# BlueSource_01.net
KiCad netlist of a schematic drawn in Altium Designer
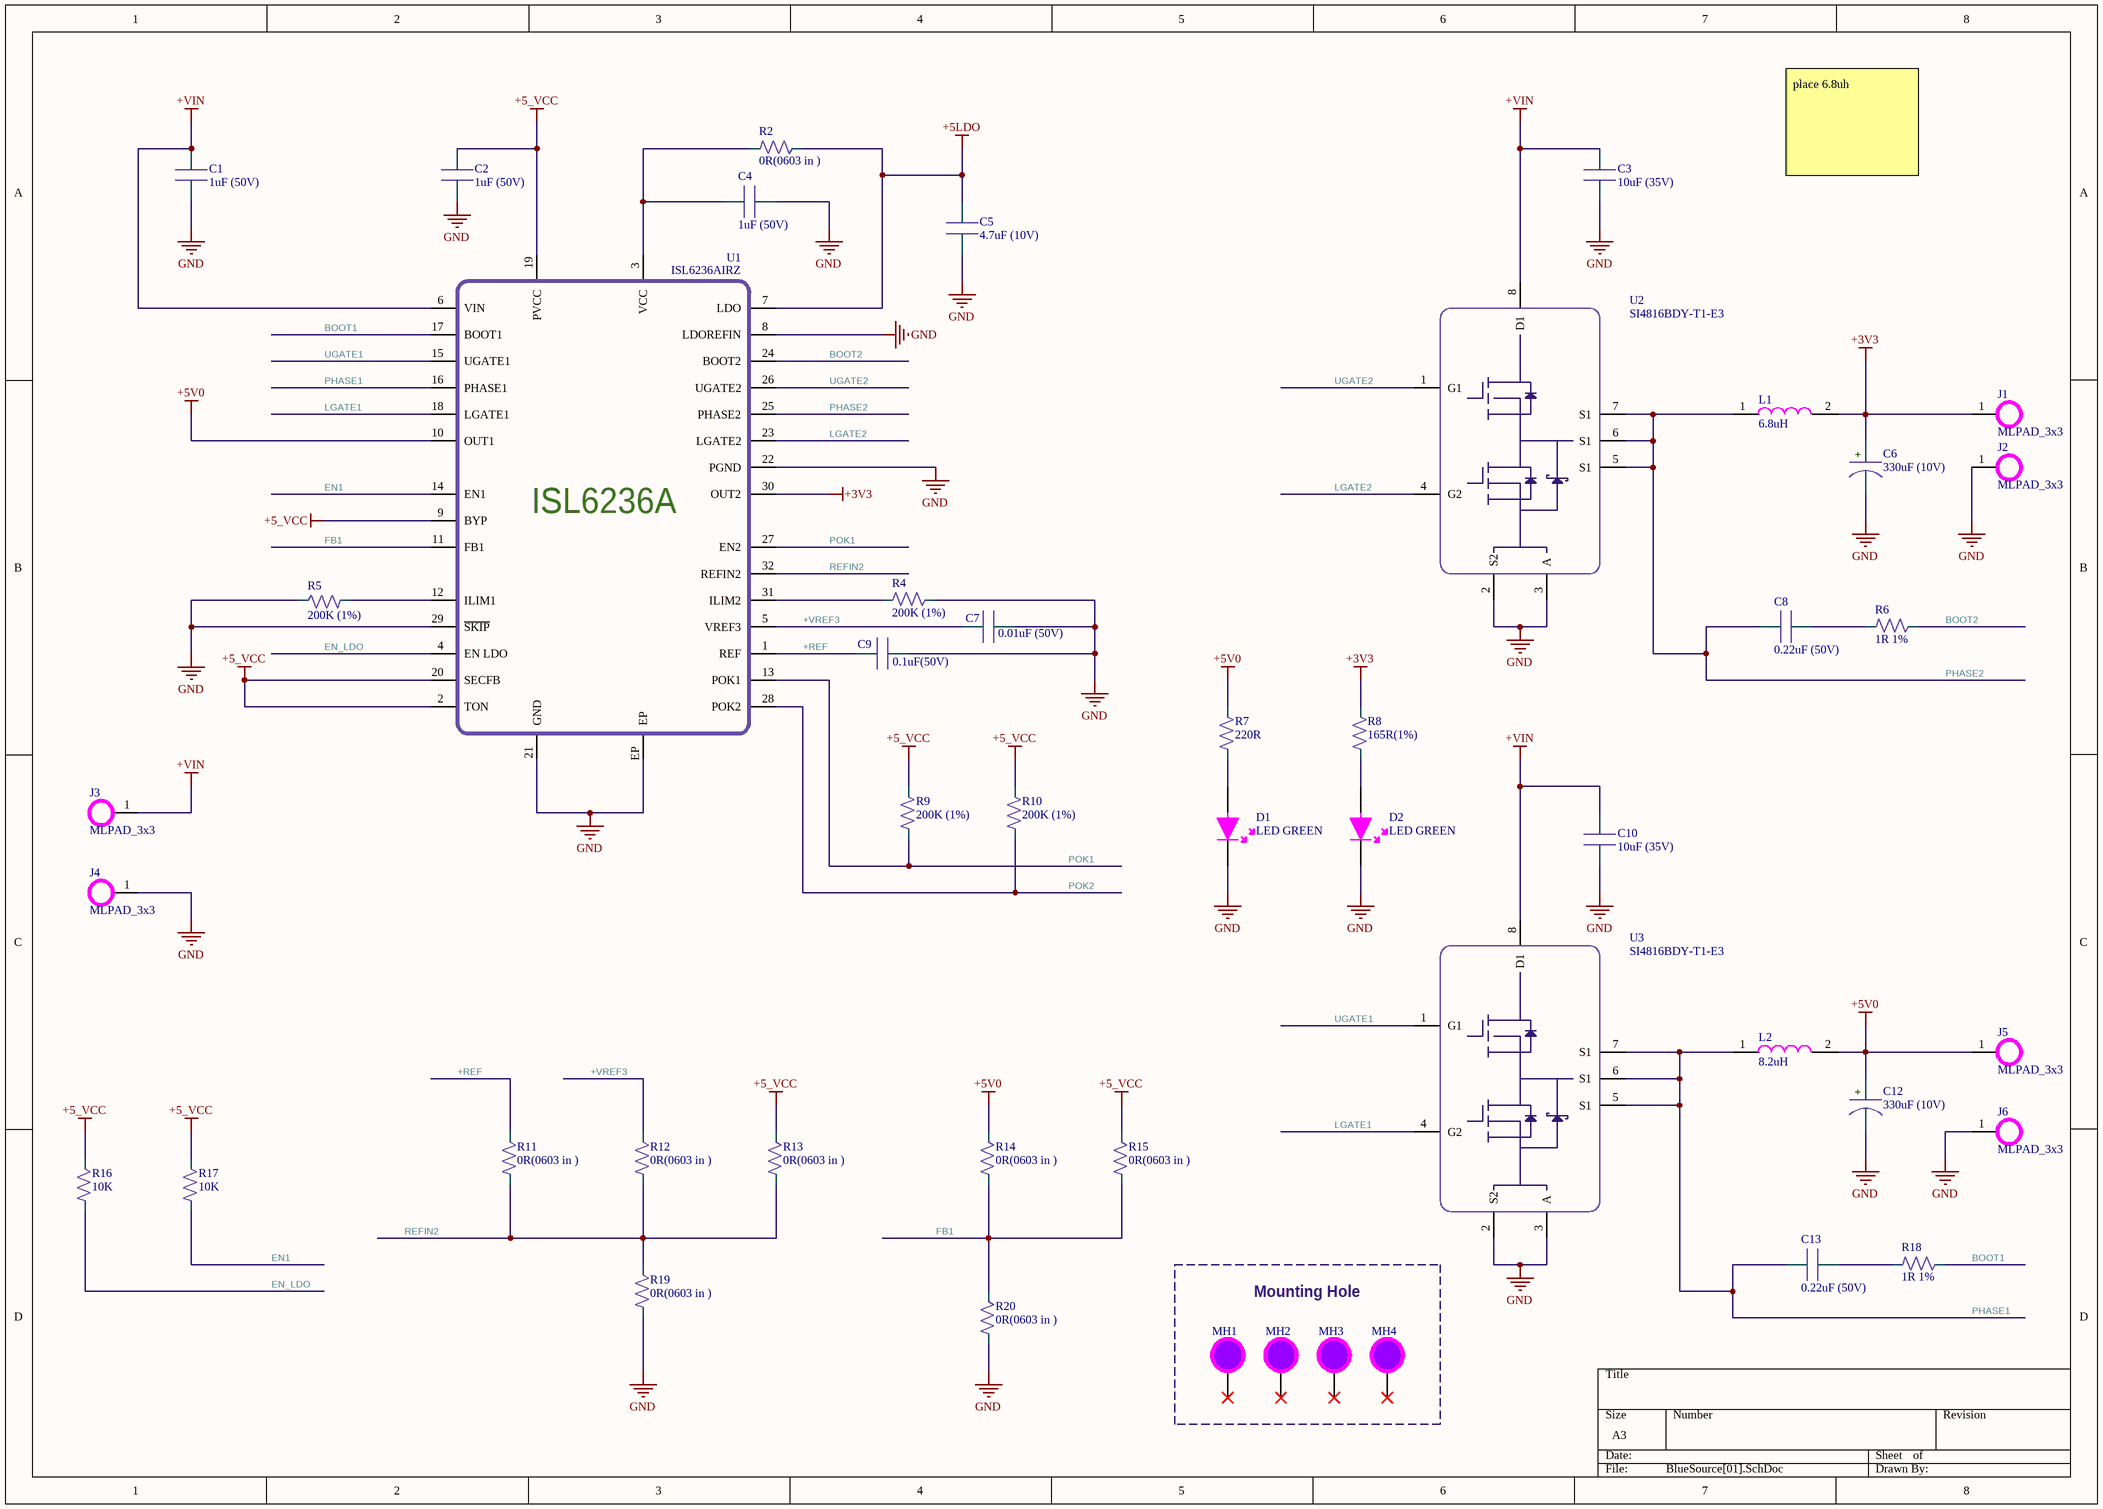
[diagram p0: BlueSource[01].SchDoc]

(export (version "E")
  (design (tool "Eeschema 10.0.6"))
  (components
    (comp (ref "C1")
      (value "1uF (50V)")
      (footprint "Capacitor_0805")
      (description "1µF ±5% 50V Ceramic Capacitor X7R 0805 (2012 Metric)")
      (fields
        (field (name "MANUFACTURERPARTNUMBER") "CC0805JKX7R9BB105")
        (field (name "MANUFACTURER") "Yageo")
      )
      (libsource (lib "Capacitors") (part "CC0805JKX7R9BB105"))
    )
    (comp (ref "C2")
      (value "1uF (50V)")
      (footprint "Capacitor_0805")
      (description "1µF ±5% 50V Ceramic Capacitor X7R 0805 (2012 Metric)")
      (fields
        (field (name "MANUFACTURERPARTNUMBER") "CC0805JKX7R9BB105")
        (field (name "MANUFACTURER") "Yageo")
      )
      (libsource (lib "Capacitors") (part "CC0805JKX7R9BB105"))
    )
    (comp (ref "C3")
      (value "10uF (35V)")
      (footprint "Capacitor_0805")
      (description "10µF ±10% 35V Ceramic Capacitor X5R 0805 (2012 Metric)")
      (fields
        (field (name "MANUFACTURERPARTNUMBER") "C2012X5R1V106K125AC")
        (field (name "MANUFACTURER") "TDK Corporation")
      )
      (libsource (lib "Capacitors") (part "C2012X5R1V106K125AC"))
    )
    (comp (ref "C4")
      (value "1uF (50V)")
      (footprint "Capacitor_0805")
      (description "1µF ±5% 50V Ceramic Capacitor X7R 0805 (2012 Metric)")
      (fields
        (field (name "MANUFACTURERPARTNUMBER") "CC0805JKX7R9BB105")
        (field (name "MANUFACTURER") "Yageo")
      )
      (libsource (lib "Capacitors") (part "CC0805JKX7R9BB105"))
    )
    (comp (ref "C5")
      (value "4.7uF (10V)")
      (footprint "Capacitor_0805")
      (description "4.7µF ±5% 10V Ceramic Capacitor X7R 0805 (2012 Metric)")
      (fields
        (field (name "MANUFACTURERPARTNUMBER") "C0805C475J8RACAUTO")
        (field (name "MANUFACTURER") "KEMET")
      )
      (libsource (lib "Capacitors") (part "C0805C475J8RACAUTO"))
    )
    (comp (ref "C6")
      (value "330uF (10V)")
      (footprint "C7343")
      (description "330µF Molded Tantalum Polymer Capacitor 10V 2917 (7343 Metric) 4mOhm @ 100kHz")
      (fields
        (field (name "MANUFACTURERPARTNUMBER") "T530X337M010ATE004")
        (field (name "MANUFACTURER") "KEMET")
      )
      (libsource (lib "Capacitors") (part "T530X337M010ATE004"))
    )
    (comp (ref "C7")
      (value "0.01uF (50V)")
      (footprint "Capacitor_0805")
      (description "10000pF ±5% 50V Ceramic Capacitor X8R 0805 (2012 Metric)")
      (fields
        (field (name "MANUFACTURERPARTNUMBER") "C0805C103J5HACAUTO")
        (field (name "MANUFACTURER") "KEMET")
      )
      (libsource (lib "Capacitors") (part "C0805C103J5HACAUTO"))
    )
    (comp (ref "C8")
      (value "0.22uF (50V)")
      (footprint "Capacitor_0805")
      (description "0.22µF ±5% 50V Ceramic Capacitor X7R 0805 (2012 Metric)")
      (fields
        (field (name "MANUFACTURERPARTNUMBER") "C0805C224J5RACAUTO")
        (field (name "MANUFACTURER") "399-C0805C224J5RACAUTOCT-ND")
      )
      (libsource (lib "Capacitors") (part "C0805C224J5RACAUTO"))
    )
    (comp (ref "C9")
      (value "0.1uF(50V)")
      (footprint "Capacitor_0805")
      (description "0.1µF ±5% 50V Ceramic Capacitor X7R 0805 (2012 Metric)")
      (fields
        (field (name "MANUFACTURERPARTNUMBER") "C0805C104J5RACTU")
        (field (name "MANUFACTURER") "KEMET")
      )
      (libsource (lib "Capacitors") (part "C0805C104J5RACTU"))
    )
    (comp (ref "C10")
      (value "10uF (35V)")
      (footprint "Capacitor_0805")
      (description "10µF ±10% 35V Ceramic Capacitor X5R 0805 (2012 Metric)")
      (fields
        (field (name "MANUFACTURERPARTNUMBER") "C2012X5R1V106K125AC")
        (field (name "MANUFACTURER") "TDK Corporation")
      )
      (libsource (lib "Capacitors") (part "C2012X5R1V106K125AC"))
    )
    (comp (ref "C12")
      (value "330uF (10V)")
      (footprint "C7343")
      (description "330µF Molded Tantalum Polymer Capacitor 10V 2917 (7343 Metric) 4mOhm @ 100kHz")
      (fields
        (field (name "MANUFACTURERPARTNUMBER") "T530X337M010ATE004")
        (field (name "MANUFACTURER") "KEMET")
      )
      (libsource (lib "Capacitors") (part "T530X337M010ATE004"))
    )
    (comp (ref "C13")
      (value "0.22uF (50V)")
      (footprint "Capacitor_0805")
      (description "0.22µF ±5% 50V Ceramic Capacitor X7R 0805 (2012 Metric)")
      (fields
        (field (name "MANUFACTURERPARTNUMBER") "C0805C224J5RACAUTO")
        (field (name "MANUFACTURER") "399-C0805C224J5RACAUTOCT-ND")
      )
      (libsource (lib "Capacitors") (part "C0805C224J5RACAUTO"))
    )
    (comp (ref "D1")
      (value "LED GREEN")
      (footprint "0603_LED")
      (description "Green 570nm LED Indication - Discrete 2.1V 0603 (1608 Metric)")
      (fields (field (name "MANUFACTURER PART NUMBER") "XZVG53W-8"))
      (libsource (lib "Diodes") (part "XZVG53W-8"))
    )
    (comp (ref "D2")
      (value "LED GREEN")
      (footprint "0603_LED")
      (description "Green 570nm LED Indication - Discrete 2.1V 0603 (1608 Metric)")
      (fields (field (name "MANUFACTURER PART NUMBER") "XZVG53W-8"))
      (libsource (lib "Diodes") (part "XZVG53W-8"))
    )
    (comp (ref "J1")
      (value "MLPAD_3x3")
      (footprint "MLPAD_3X3")
      (libsource (lib "connectors") (part "MLPAD_3X3"))
    )
    (comp (ref "J2")
      (value "MLPAD_3x3")
      (footprint "MLPAD_3X3")
      (libsource (lib "connectors") (part "MLPAD_3X3"))
    )
    (comp (ref "J3")
      (value "MLPAD_3x3")
      (footprint "MLPAD_3X3")
      (libsource (lib "connectors") (part "MLPAD_3X3"))
    )
    (comp (ref "J4")
      (value "MLPAD_3x3")
      (footprint "MLPAD_3X3")
      (libsource (lib "connectors") (part "MLPAD_3X3"))
    )
    (comp (ref "J5")
      (value "MLPAD_3x3")
      (footprint "MLPAD_3X3")
      (libsource (lib "connectors") (part "MLPAD_3X3"))
    )
    (comp (ref "J6")
      (value "MLPAD_3x3")
      (footprint "MLPAD_3X3")
      (libsource (lib "connectors") (part "MLPAD_3X3"))
    )
    (comp (ref "L1")
      (value "6.8uH")
      (footprint "DR125_Inductor")
      (description "6.8µH Shielded Wirewound Inductor 6.64A 12.3mOhm Nonstandard")
      (fields
        (field (name "MANUFACTURERPARTNUMBER") "DR125-6R8-R")
        (field (name "MANUFACTURER") "Eaton - Electronics Division")
      )
      (libsource (lib "inductors and coils") (part "DR125-6R8-R"))
    )
    (comp (ref "L2")
      (value "8.2uH")
      (footprint "DR125_Inductor")
      (description "8.2µH Shielded Wirewound Inductor 5.54A 17.6mOhm Nonstandard")
      (fields
        (field (name "MANUFACTURERPARTNUMBER") "DR125-8R2-R")
        (field (name "MANUFACTURER") "Eaton - Electronics Division")
      )
      (libsource (lib "inductors and coils") (part "DR125-8R2-R"))
    )
    (comp (ref "MH1")
      (value "Mounting Hole")
      (footprint "Mounting_Hole_3.3mm")
      (description "3.3mm Mounting Hole")
      (libsource (lib "connectors") (part "3MM_MOUNTING_HOLE"))
    )
    (comp (ref "MH2")
      (value "Mounting Hole")
      (footprint "Mounting_Hole_3.3mm")
      (description "3.3mm Mounting Hole")
      (libsource (lib "connectors") (part "3MM_MOUNTING_HOLE"))
    )
    (comp (ref "MH3")
      (value "Mounting Hole")
      (footprint "Mounting_Hole_3.3mm")
      (description "3.3mm Mounting Hole")
      (libsource (lib "connectors") (part "3MM_MOUNTING_HOLE"))
    )
    (comp (ref "MH4")
      (value "Mounting Hole")
      (footprint "Mounting_Hole_3.3mm")
      (description "3.3mm Mounting Hole")
      (libsource (lib "connectors") (part "3MM_MOUNTING_HOLE"))
    )
    (comp (ref "R2")
      (value "0R(0603 in )")
      (footprint "RESISTOR0603")
      (description "0 Ohms Jumper 0.1W, 1/10W Chip Resistor 0603 (1608 Metric) Automotive AEC-Q200 Thick Film")
      (fields (field (name "MANUFACTURER PART NUMBER") "RMCF0603ZT0R00"))
      (libsource (lib "Resistors") (part "RMCF0603ZT0R00"))
    )
    (comp (ref "R4")
      (value "200K (1%)")
      (footprint "RESISTOR0805")
      (description "200 kOhms ±1% 0.125W, 1/8W Chip Resistor 0805 (2012 Metric) Automotive AEC-Q200 Thick Film")
      (fields
        (field (name "MANUFACTURERPARTNUMBER") "ERJ-6ENF2003V")
        (field (name "MANUFACTURER") "Panasonic Electronic Components")
      )
      (libsource (lib "Resistors") (part "ERJ-6ENF2003V"))
    )
    (comp (ref "R5")
      (value "200K (1%)")
      (footprint "RESISTOR0805")
      (description "200 kOhms ±1% 0.125W, 1/8W Chip Resistor 0805 (2012 Metric) Automotive AEC-Q200 Thick Film")
      (fields
        (field (name "MANUFACTURERPARTNUMBER") "ERJ-6ENF2003V")
        (field (name "MANUFACTURER") "Panasonic Electronic Components")
      )
      (libsource (lib "Resistors") (part "ERJ-6ENF2003V"))
    )
    (comp (ref "R6")
      (value "1R 1%")
      (footprint "RESISTOR0805")
      (fields
        (field (name "MANUFACTURERPARTNUMBER") "ERJ-6RQF1R0V")
        (field (name "MANUFACTURER") "Panasonic Electronic Components")
      )
      (libsource (lib "Resistors") (part "ERJ-6RQF1R0V"))
    )
    (comp (ref "R7")
      (value "220R")
      (footprint "RESISTOR0603")
      (description "220 Ohms ±5% 0.1W, 1/10W Chip Resistor 0603 (1608 Metric) Automotive AEC-Q200 Thick Film")
      (fields
        (field (name "MANUFACTURERPARTNUMBER") "RMCF0603JT220R")
        (field (name "MANUFACTURER") "Stackpole Electronics Inc")
      )
      (libsource (lib "Resistors") (part "RMCF0603JT220R"))
    )
    (comp (ref "R8")
      (value "165R(1%)")
      (footprint "RESISTOR0603")
      (description "165 Ohms ±1% 0.1W, 1/10W Chip Resistor 0603 (1608 Metric) Automotive AEC-Q200 Thick Film")
      (fields
        (field (name "MANUFACTURERPARTNUMBER") "RMCF0603FT165R")
        (field (name "MANUFACTURER") "Stackpole Electronics Inc")
      )
      (libsource (lib "Resistors") (part "RMCF0603FT165R"))
    )
    (comp (ref "R9")
      (value "200K (1%)")
      (footprint "RESISTOR0805")
      (description "200 kOhms ±1% 0.125W, 1/8W Chip Resistor 0805 (2012 Metric) Automotive AEC-Q200 Thick Film")
      (fields
        (field (name "MANUFACTURERPARTNUMBER") "ERJ-6ENF2003V")
        (field (name "MANUFACTURER") "Panasonic Electronic Components")
      )
      (libsource (lib "Resistors") (part "ERJ-6ENF2003V"))
    )
    (comp (ref "R10")
      (value "200K (1%)")
      (footprint "RESISTOR0805")
      (description "200 kOhms ±1% 0.125W, 1/8W Chip Resistor 0805 (2012 Metric) Automotive AEC-Q200 Thick Film")
      (fields
        (field (name "MANUFACTURERPARTNUMBER") "ERJ-6ENF2003V")
        (field (name "MANUFACTURER") "Panasonic Electronic Components")
      )
      (libsource (lib "Resistors") (part "ERJ-6ENF2003V"))
    )
    (comp (ref "R11")
      (value "0R(0603 in )")
      (footprint "RESISTOR0603")
      (description "0 Ohms Jumper 0.1W, 1/10W Chip Resistor 0603 (1608 Metric) Automotive AEC-Q200 Thick Film")
      (fields (field (name "MANUFACTURER PART NUMBER") "RMCF0603ZT0R00"))
      (libsource (lib "Resistors") (part "RMCF0603ZT0R00"))
    )
    (comp (ref "R12")
      (value "0R(0603 in )")
      (footprint "RESISTOR0603")
      (description "0 Ohms Jumper 0.1W, 1/10W Chip Resistor 0603 (1608 Metric) Automotive AEC-Q200 Thick Film")
      (fields (field (name "MANUFACTURER PART NUMBER") "RMCF0603ZT0R00"))
      (libsource (lib "Resistors") (part "RMCF0603ZT0R00"))
    )
    (comp (ref "R13")
      (value "0R(0603 in )")
      (footprint "RESISTOR0603")
      (description "0 Ohms Jumper 0.1W, 1/10W Chip Resistor 0603 (1608 Metric) Automotive AEC-Q200 Thick Film")
      (fields (field (name "MANUFACTURER PART NUMBER") "RMCF0603ZT0R00"))
      (libsource (lib "Resistors") (part "RMCF0603ZT0R00"))
    )
    (comp (ref "R14")
      (value "0R(0603 in )")
      (footprint "RESISTOR0603")
      (description "0 Ohms Jumper 0.1W, 1/10W Chip Resistor 0603 (1608 Metric) Automotive AEC-Q200 Thick Film")
      (fields (field (name "MANUFACTURER PART NUMBER") "RMCF0603ZT0R00"))
      (libsource (lib "Resistors") (part "RMCF0603ZT0R00"))
    )
    (comp (ref "R15")
      (value "0R(0603 in )")
      (footprint "RESISTOR0603")
      (description "0 Ohms Jumper 0.1W, 1/10W Chip Resistor 0603 (1608 Metric) Automotive AEC-Q200 Thick Film")
      (fields (field (name "MANUFACTURER PART NUMBER") "RMCF0603ZT0R00"))
      (libsource (lib "Resistors") (part "RMCF0603ZT0R00"))
    )
    (comp (ref "R16")
      (value "10K")
      (footprint "RESISTOR0805")
      (description "10 kOhms ±5% 0.125W, 1/8W Chip Resistor 0805 (2012 Metric) Automotive AEC-Q200 Thick Film")
      (fields
        (field (name "MANUFACTURERPARTNUMBER") "ERJ-6GEYJ103V")
        (field (name "MANUFACTURER") "Panasonic Electronic Components")
      )
      (libsource (lib "Resistors") (part "ERJ-6GEYJ103V"))
    )
    (comp (ref "R17")
      (value "10K")
      (footprint "RESISTOR0805")
      (description "10 kOhms ±5% 0.125W, 1/8W Chip Resistor 0805 (2012 Metric) Automotive AEC-Q200 Thick Film")
      (fields
        (field (name "MANUFACTURERPARTNUMBER") "ERJ-6GEYJ103V")
        (field (name "MANUFACTURER") "Panasonic Electronic Components")
      )
      (libsource (lib "Resistors") (part "ERJ-6GEYJ103V"))
    )
    (comp (ref "R18")
      (value "1R 1%")
      (footprint "RESISTOR0805")
      (fields
        (field (name "MANUFACTURERPARTNUMBER") "ERJ-6RQF1R0V")
        (field (name "MANUFACTURER") "Panasonic Electronic Components")
      )
      (libsource (lib "Resistors") (part "ERJ-6RQF1R0V"))
    )
    (comp (ref "R19")
      (value "0R(0603 in )")
      (footprint "RESISTOR0603")
      (description "0 Ohms Jumper 0.1W, 1/10W Chip Resistor 0603 (1608 Metric) Automotive AEC-Q200 Thick Film")
      (fields (field (name "MANUFACTURER PART NUMBER") "RMCF0603ZT0R00"))
      (libsource (lib "Resistors") (part "RMCF0603ZT0R00"))
    )
    (comp (ref "R20")
      (value "0R(0603 in )")
      (footprint "RESISTOR0603")
      (description "0 Ohms Jumper 0.1W, 1/10W Chip Resistor 0603 (1608 Metric) Automotive AEC-Q200 Thick Film")
      (fields (field (name "MANUFACTURER PART NUMBER") "RMCF0603ZT0R00"))
      (libsource (lib "Resistors") (part "RMCF0603ZT0R00"))
    )
    (comp (ref "U1")
      (value "ISL6236AIRZ")
      (footprint "32QFN")
      (description "- Controller, Notebook Power System Voltage Regulator IC 4 Output 32-QFN (5x5)")
      (fields (field (name "MANUFACTURER") "Renesas Electronics America Inc"))
      (libsource (lib "integrated_circuits") (part "ISL6236AIRZ"))
    )
    (comp (ref "U2")
      (value "SI4816BDY-T1-E3")
      (footprint "SOIC-8")
      (description "Mosfet Array 2 N-Channel (Half Bridge) 30V 5.8A, 8.2A 1W, 1.25W Surface Mount 8-SO")
      (fields (field (name "MANUFACTURER") "Vishay Siliconix"))
      (libsource (lib "integrated_circuits") (part "SI4816BDY-T1-E3"))
    )
    (comp (ref "U3")
      (value "SI4816BDY-T1-E3")
      (footprint "SOIC-8")
      (description "Mosfet Array 2 N-Channel (Half Bridge) 30V 5.8A, 8.2A 1W, 1.25W Surface Mount 8-SO")
      (fields (field (name "MANUFACTURER") "Vishay Siliconix"))
      (libsource (lib "integrated_circuits") (part "SI4816BDY-T1-E3"))
    )
  )
  (nets
    (net (code "1") (name "+3V3") (class "Default")
      (node (ref "C6") (pin "2") (pinfunction "2_2") (pintype "passive"))
      (node (ref "J1") (pin "1") (pinfunction "1_1") (pintype "passive"))
      (node (ref "L1") (pin "2") (pinfunction "2_2") (pintype "passive"))
      (node (ref "R8") (pin "2") (pinfunction "2_2") (pintype "passive"))
      (node (ref "U1") (pin "30") (pinfunction "OUT2_30") (pintype "passive"))
    )
    (net (code "2") (name "+5LDO") (class "Default")
      (node (ref "C5") (pin "2") (pinfunction "2_2") (pintype "passive"))
      (node (ref "R2") (pin "2") (pinfunction "2_2") (pintype "passive"))
      (node (ref "U1") (pin "7") (pinfunction "LDO_7") (pintype "passive"))
    )
    (net (code "3") (name "+5V0") (class "Default")
      (node (ref "C12") (pin "2") (pinfunction "2_2") (pintype "passive"))
      (node (ref "J5") (pin "1") (pinfunction "1_1") (pintype "passive"))
      (node (ref "L2") (pin "2") (pinfunction "2_2") (pintype "passive"))
      (node (ref "R14") (pin "2") (pinfunction "2_2") (pintype "passive"))
      (node (ref "R7") (pin "2") (pinfunction "2_2") (pintype "passive"))
      (node (ref "U1") (pin "10") (pinfunction "OUT1_10") (pintype "passive"))
    )
    (net (code "4") (name "+5_VCC") (class "Default")
      (node (ref "C2") (pin "2") (pinfunction "2_2") (pintype "passive"))
      (node (ref "R10") (pin "2") (pinfunction "2_2") (pintype "passive"))
      (node (ref "R13") (pin "2") (pinfunction "2_2") (pintype "passive"))
      (node (ref "R15") (pin "2") (pinfunction "2_2") (pintype "passive"))
      (node (ref "R16") (pin "2") (pinfunction "2_2") (pintype "passive"))
      (node (ref "R17") (pin "2") (pinfunction "2_2") (pintype "passive"))
      (node (ref "R9") (pin "2") (pinfunction "2_2") (pintype "passive"))
      (node (ref "U1") (pin "19") (pinfunction "PVCC_19") (pintype "passive"))
      (node (ref "U1") (pin "2") (pinfunction "TON_2") (pintype "passive"))
      (node (ref "U1") (pin "20") (pinfunction "SECFB_20") (pintype "passive"))
      (node (ref "U1") (pin "9") (pinfunction "BYP_9") (pintype "passive"))
    )
    (net (code "5") (name "+VIN") (class "Default")
      (node (ref "C1") (pin "2") (pinfunction "2_2") (pintype "passive"))
      (node (ref "C10") (pin "2") (pinfunction "2_2") (pintype "passive"))
      (node (ref "C3") (pin "2") (pinfunction "2_2") (pintype "passive"))
      (node (ref "J3") (pin "1") (pinfunction "1_1") (pintype "passive"))
      (node (ref "U1") (pin "6") (pinfunction "VIN_6") (pintype "passive"))
      (node (ref "U2") (pin "8") (pinfunction "D1_8") (pintype "passive"))
      (node (ref "U3") (pin "8") (pinfunction "D1_8") (pintype "passive"))
    )
    (net (code "6") (name "/+REF") (class "Default")
      (node (ref "C9") (pin "1") (pinfunction "1_1") (pintype "passive"))
      (node (ref "R11") (pin "2") (pinfunction "2_2") (pintype "passive"))
      (node (ref "U1") (pin "1") (pinfunction "REF_1") (pintype "passive"))
    )
    (net (code "7") (name "/+VREF3") (class "Default")
      (node (ref "C7") (pin "1") (pinfunction "1_1") (pintype "passive"))
      (node (ref "R12") (pin "2") (pinfunction "2_2") (pintype "passive"))
      (node (ref "U1") (pin "5") (pinfunction "VREF3_5") (pintype "passive"))
    )
    (net (code "8") (name "/BOOT1") (class "Default")
      (node (ref "R18") (pin "2") (pinfunction "2_2") (pintype "passive"))
      (node (ref "U1") (pin "17") (pinfunction "BOOT1_17") (pintype "passive"))
    )
    (net (code "9") (name "/BOOT2") (class "Default")
      (node (ref "R6") (pin "2") (pinfunction "2_2") (pintype "passive"))
      (node (ref "U1") (pin "24") (pinfunction "BOOT2_24") (pintype "passive"))
    )
    (net (code "10") (name "/EN1") (class "Default")
      (node (ref "R17") (pin "1") (pinfunction "1_1") (pintype "passive"))
      (node (ref "U1") (pin "14") (pinfunction "EN1_14") (pintype "passive"))
    )
    (net (code "11") (name "/EN_LDO") (class "Default")
      (node (ref "R16") (pin "1") (pinfunction "1_1") (pintype "passive"))
      (node (ref "U1") (pin "4") (pinfunction "EN_LDO_4") (pintype "passive"))
    )
    (net (code "12") (name "/FB1") (class "Default")
      (node (ref "R14") (pin "1") (pinfunction "1_1") (pintype "passive"))
      (node (ref "R15") (pin "1") (pinfunction "1_1") (pintype "passive"))
      (node (ref "R20") (pin "2") (pinfunction "2_2") (pintype "passive"))
      (node (ref "U1") (pin "11") (pinfunction "FB1_11") (pintype "passive"))
    )
    (net (code "13") (name "/LGATE1") (class "Default")
      (node (ref "U1") (pin "18") (pinfunction "LGATE1_18") (pintype "passive"))
      (node (ref "U3") (pin "4") (pinfunction "G2_4") (pintype "passive"))
    )
    (net (code "14") (name "/LGATE2") (class "Default")
      (node (ref "U1") (pin "23") (pinfunction "LGATE2_23") (pintype "passive"))
      (node (ref "U2") (pin "4") (pinfunction "G2_4") (pintype "passive"))
    )
    (net (code "15") (name "/PHASE1") (class "Default")
      (node (ref "C13") (pin "1") (pinfunction "1_1") (pintype "passive"))
      (node (ref "L2") (pin "1") (pinfunction "1_1") (pintype "passive"))
      (node (ref "U1") (pin "16") (pinfunction "PHASE1_16") (pintype "passive"))
      (node (ref "U3") (pin "5") (pinfunction "S1_5") (pintype "passive"))
      (node (ref "U3") (pin "6") (pinfunction "S1_6") (pintype "passive"))
      (node (ref "U3") (pin "7") (pinfunction "S1_7") (pintype "passive"))
    )
    (net (code "16") (name "/PHASE2") (class "Default")
      (node (ref "C8") (pin "1") (pinfunction "1_1") (pintype "passive"))
      (node (ref "L1") (pin "1") (pinfunction "1_1") (pintype "passive"))
      (node (ref "U1") (pin "25") (pinfunction "PHASE2_25") (pintype "passive"))
      (node (ref "U2") (pin "5") (pinfunction "S1_5") (pintype "passive"))
      (node (ref "U2") (pin "6") (pinfunction "S1_6") (pintype "passive"))
      (node (ref "U2") (pin "7") (pinfunction "S1_7") (pintype "passive"))
    )
    (net (code "17") (name "/POK1") (class "Default")
      (node (ref "R9") (pin "1") (pinfunction "1_1") (pintype "passive"))
      (node (ref "U1") (pin "13") (pinfunction "POK1_13") (pintype "passive"))
      (node (ref "U1") (pin "27") (pinfunction "EN2_27") (pintype "passive"))
    )
    (net (code "18") (name "/POK2") (class "Default")
      (node (ref "R10") (pin "1") (pinfunction "1_1") (pintype "passive"))
      (node (ref "U1") (pin "28") (pinfunction "POK2_28") (pintype "passive"))
    )
    (net (code "19") (name "/REFIN2") (class "Default")
      (node (ref "R11") (pin "1") (pinfunction "1_1") (pintype "passive"))
      (node (ref "R12") (pin "1") (pinfunction "1_1") (pintype "passive"))
      (node (ref "R13") (pin "1") (pinfunction "1_1") (pintype "passive"))
      (node (ref "R19") (pin "2") (pinfunction "2_2") (pintype "passive"))
      (node (ref "U1") (pin "32") (pinfunction "REFIN2_32") (pintype "passive"))
    )
    (net (code "20") (name "/UGATE1") (class "Default")
      (node (ref "U1") (pin "15") (pinfunction "UGATE1_15") (pintype "passive"))
      (node (ref "U3") (pin "1") (pinfunction "G1_1") (pintype "passive"))
    )
    (net (code "21") (name "/UGATE2") (class "Default")
      (node (ref "U1") (pin "26") (pinfunction "UGATE2_26") (pintype "passive"))
      (node (ref "U2") (pin "1") (pinfunction "G1_1") (pintype "passive"))
    )
    (net (code "22") (name "GND") (class "Default")
      (node (ref "C1") (pin "1") (pinfunction "1_1") (pintype "passive"))
      (node (ref "C10") (pin "1") (pinfunction "1_1") (pintype "passive"))
      (node (ref "C12") (pin "1") (pinfunction "1_1") (pintype "passive"))
      (node (ref "C2") (pin "1") (pinfunction "1_1") (pintype "passive"))
      (node (ref "C3") (pin "1") (pinfunction "1_1") (pintype "passive"))
      (node (ref "C4") (pin "2") (pinfunction "2_2") (pintype "passive"))
      (node (ref "C5") (pin "1") (pinfunction "1_1") (pintype "passive"))
      (node (ref "C6") (pin "1") (pinfunction "1_1") (pintype "passive"))
      (node (ref "C7") (pin "2") (pinfunction "2_2") (pintype "passive"))
      (node (ref "C9") (pin "2") (pinfunction "2_2") (pintype "passive"))
      (node (ref "D1") (pin "2") (pinfunction "2_2") (pintype "passive"))
      (node (ref "D2") (pin "2") (pinfunction "2_2") (pintype "passive"))
      (node (ref "J2") (pin "1") (pinfunction "1_1") (pintype "passive"))
      (node (ref "J4") (pin "1") (pinfunction "1_1") (pintype "passive"))
      (node (ref "J6") (pin "1") (pinfunction "1_1") (pintype "passive"))
      (node (ref "R19") (pin "1") (pinfunction "1_1") (pintype "passive"))
      (node (ref "R20") (pin "1") (pinfunction "1_1") (pintype "passive"))
      (node (ref "R4") (pin "2") (pinfunction "2_2") (pintype "passive"))
      (node (ref "R5") (pin "2") (pinfunction "2_2") (pintype "passive"))
      (node (ref "U1") (pin "21") (pinfunction "GND_21") (pintype "passive"))
      (node (ref "U1") (pin "22") (pinfunction "PGND_22") (pintype "passive"))
      (node (ref "U1") (pin "29") (pinfunction "~{SKIP}_29") (pintype "passive"))
      (node (ref "U1") (pin "8") (pinfunction "LDOREFIN_8") (pintype "passive"))
      (node (ref "U1") (pin "EP") (pinfunction "EP_EP") (pintype "passive"))
      (node (ref "U2") (pin "2") (pinfunction "S2_2") (pintype "passive"))
      (node (ref "U2") (pin "3") (pinfunction "A_3") (pintype "passive"))
      (node (ref "U3") (pin "2") (pinfunction "S2_2") (pintype "passive"))
      (node (ref "U3") (pin "3") (pinfunction "A_3") (pintype "passive"))
    )
    (net (code "23") (name "Net-(C8-Pad2)") (class "Default")
      (node (ref "C8") (pin "2") (pinfunction "2_2") (pintype "passive"))
      (node (ref "R6") (pin "1") (pinfunction "1_1") (pintype "passive"))
    )
    (net (code "24") (name "Net-(C13-Pad2)") (class "Default")
      (node (ref "C13") (pin "2") (pinfunction "2_2") (pintype "passive"))
      (node (ref "R18") (pin "1") (pinfunction "1_1") (pintype "passive"))
    )
    (net (code "25") (name "Net-(D1-Pad1)") (class "Default")
      (node (ref "D1") (pin "1") (pinfunction "1_1") (pintype "passive"))
      (node (ref "R7") (pin "1") (pinfunction "1_1") (pintype "passive"))
    )
    (net (code "26") (name "Net-(D2-Pad1)") (class "Default")
      (node (ref "D2") (pin "1") (pinfunction "1_1") (pintype "passive"))
      (node (ref "R8") (pin "1") (pinfunction "1_1") (pintype "passive"))
    )
    (net (code "27") (name "Net-(U1-ILIM1)") (class "Default")
      (node (ref "R5") (pin "1") (pinfunction "1_1") (pintype "passive"))
      (node (ref "U1") (pin "12") (pinfunction "ILIM1_12") (pintype "passive"))
    )
    (net (code "28") (name "Net-(U1-ILIM2)") (class "Default")
      (node (ref "R4") (pin "1") (pinfunction "1_1") (pintype "passive"))
      (node (ref "U1") (pin "31") (pinfunction "ILIM2_31") (pintype "passive"))
    )
    (net (code "29") (name "Net-(U1-VCC)") (class "Default")
      (node (ref "C4") (pin "1") (pinfunction "1_1") (pintype "passive"))
      (node (ref "R2") (pin "1") (pinfunction "1_1") (pintype "passive"))
      (node (ref "U1") (pin "3") (pinfunction "VCC_3") (pintype "passive"))
    )
    (net (code "30") (name "unconnected-(MH1-Pad1)") (class "Default")
      (node (ref "MH1") (pin "1") (pinfunction "1_1") (pintype "passive+no_connect"))
    )
    (net (code "31") (name "unconnected-(MH2-Pad1)") (class "Default")
      (node (ref "MH2") (pin "1") (pinfunction "1_1") (pintype "passive+no_connect"))
    )
    (net (code "32") (name "unconnected-(MH3-Pad1)") (class "Default")
      (node (ref "MH3") (pin "1") (pinfunction "1_1") (pintype "passive+no_connect"))
    )
    (net (code "33") (name "unconnected-(MH4-Pad1)") (class "Default")
      (node (ref "MH4") (pin "1") (pinfunction "1_1") (pintype "passive+no_connect"))
    )
  )
)
